# DoDecaCharlieCylonCR2032.net
KiCad netlist of a schematic drawn in EAGLE
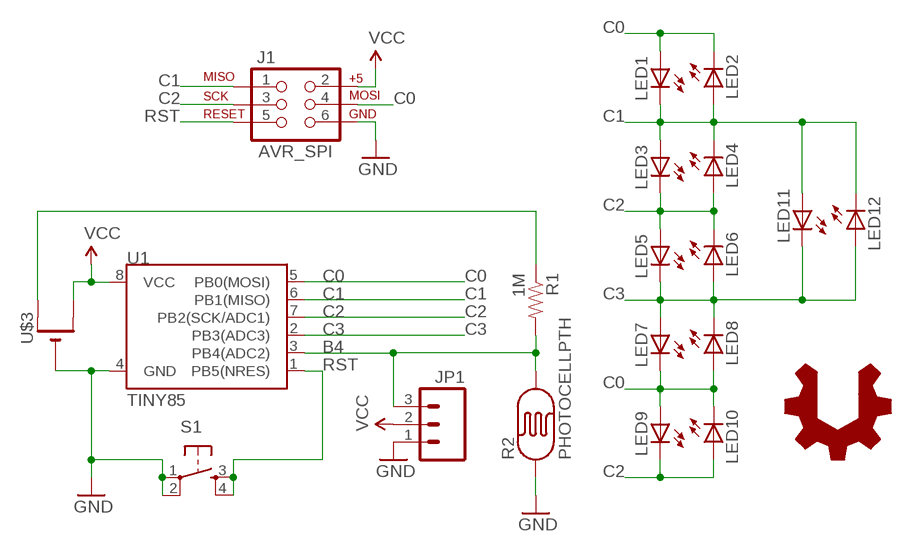
[diagram p0: schematic, sheet 1]

(export (version "E")
  (design (tool "Eeschema 10.0.6"))
  (components
    (comp (ref "J1")
      (value "AVR_SPI")
      (footprint "eagle-import:2X3-NS")
      (libsource (lib "eagle-import") (part "AVR_SPI_PRG_6LABELED"))
    )
    (comp (ref "JP1")
      (value "M03PTH")
      (footprint "eagle-import:1X03")
      (libsource (lib "eagle-import") (part "M03PTH"))
    )
    (comp (ref "LED1")
      (value "LEDOVAL")
      (footprint "eagle-import:LED-OVAL")
      (libsource (lib "eagle-import") (part "LEDOVAL"))
    )
    (comp (ref "LED2")
      (value "LEDOVAL")
      (footprint "eagle-import:LED-OVAL")
      (libsource (lib "eagle-import") (part "LEDOVAL"))
    )
    (comp (ref "LED3")
      (value "LEDOVAL")
      (footprint "eagle-import:LED-OVAL")
      (libsource (lib "eagle-import") (part "LEDOVAL"))
    )
    (comp (ref "LED4")
      (value "LEDOVAL")
      (footprint "eagle-import:LED-OVAL")
      (libsource (lib "eagle-import") (part "LEDOVAL"))
    )
    (comp (ref "LED5")
      (value "LEDOVAL")
      (footprint "eagle-import:LED-OVAL")
      (libsource (lib "eagle-import") (part "LEDOVAL"))
    )
    (comp (ref "LED6")
      (value "LEDOVAL")
      (footprint "eagle-import:LED-OVAL")
      (libsource (lib "eagle-import") (part "LEDOVAL"))
    )
    (comp (ref "LED7")
      (value "LEDOVAL")
      (footprint "eagle-import:LED-OVAL")
      (libsource (lib "eagle-import") (part "LEDOVAL"))
    )
    (comp (ref "LED8")
      (value "LEDOVAL")
      (footprint "eagle-import:LED-OVAL")
      (libsource (lib "eagle-import") (part "LEDOVAL"))
    )
    (comp (ref "LED9")
      (value "LEDOVAL")
      (footprint "eagle-import:LED-OVAL")
      (libsource (lib "eagle-import") (part "LEDOVAL"))
    )
    (comp (ref "LED10")
      (value "LEDOVAL")
      (footprint "eagle-import:LED-OVAL")
      (libsource (lib "eagle-import") (part "LEDOVAL"))
    )
    (comp (ref "LED11")
      (value "LEDOVAL")
      (footprint "eagle-import:LED-OVAL")
      (libsource (lib "eagle-import") (part "LEDOVAL"))
    )
    (comp (ref "LED12")
      (value "LEDOVAL")
      (footprint "eagle-import:LED-OVAL")
      (libsource (lib "eagle-import") (part "LEDOVAL"))
    )
    (comp (ref "R1")
      (value "1M")
      (footprint "eagle-import:AXIAL-0.3")
      (libsource (lib "eagle-import") (part "RESISTORAXIAL-0.3"))
    )
    (comp (ref "R2")
      (value "PHOTOCELLPTH")
      (footprint "eagle-import:PHOTOCELL")
      (libsource (lib "eagle-import") (part "PHOTOCELLPTH"))
    )
    (comp (ref "S1")
      (value "TAC_SWITCHPTH")
      (footprint "eagle-import:TACTILE-PTH")
      (libsource (lib "eagle-import") (part "TAC_SWITCHPTH"))
    )
    (comp (ref "U$1")
      (value "USER_HACKABLE")
      (footprint "eagle-import:USER_HACKABLE")
      (libsource (lib "eagle-import") (part "USER_HACKABLE"))
    )
    (comp (ref "U$3")
      (value "CR2032THM")
      (footprint "eagle-import:CR2032-THRU")
      (libsource (lib "eagle-import") (part "CR2032THM"))
    )
    (comp (ref "U1")
      (value "TINY85")
      (footprint "eagle-import:DIP08")
      (libsource (lib "eagle-import") (part "ATTINY45TINY85-20-DIP"))
    )
  )
  (nets
    (net (code "1") (name "/B4") (class "Default")
      (node (ref "JP1") (pin "3") (pinfunction "3_3") (pintype "passive"))
      (node (ref "R1") (pin "P$2") (pinfunction "2_P$2") (pintype "passive"))
      (node (ref "R2") (pin "2") (pinfunction "P$2_2") (pintype "bidirectional"))
      (node (ref "U1") (pin "3") (pinfunction "PB4(ADC2)_3") (pintype "bidirectional"))
    )
    (net (code "2") (name "/C0") (class "Default")
      (node (ref "J1") (pin "4") (pinfunction "MOSI_4") (pintype "passive"))
      (node (ref "LED1") (pin "ANODE") (pinfunction "A_ANODE") (pintype "passive"))
      (node (ref "LED10") (pin "CATHODE") (pinfunction "C_CATHODE") (pintype "passive"))
      (node (ref "LED2") (pin "CATHODE") (pinfunction "C_CATHODE") (pintype "passive"))
      (node (ref "LED7") (pin "CATHODE") (pinfunction "C_CATHODE") (pintype "passive"))
      (node (ref "LED8") (pin "ANODE") (pinfunction "A_ANODE") (pintype "passive"))
      (node (ref "LED9") (pin "ANODE") (pinfunction "A_ANODE") (pintype "passive"))
      (node (ref "U1") (pin "5") (pinfunction "PB0(MOSI)_5") (pintype "bidirectional"))
    )
    (net (code "3") (name "/C1") (class "Default")
      (node (ref "J1") (pin "1") (pinfunction "MISO_1") (pintype "passive"))
      (node (ref "LED1") (pin "CATHODE") (pinfunction "C_CATHODE") (pintype "passive"))
      (node (ref "LED11") (pin "ANODE") (pinfunction "A_ANODE") (pintype "passive"))
      (node (ref "LED12") (pin "CATHODE") (pinfunction "C_CATHODE") (pintype "passive"))
      (node (ref "LED2") (pin "ANODE") (pinfunction "A_ANODE") (pintype "passive"))
      (node (ref "LED3") (pin "ANODE") (pinfunction "A_ANODE") (pintype "passive"))
      (node (ref "LED4") (pin "CATHODE") (pinfunction "C_CATHODE") (pintype "passive"))
      (node (ref "U1") (pin "6") (pinfunction "PB1(MISO)_6") (pintype "bidirectional"))
    )
    (net (code "4") (name "/C2") (class "Default")
      (node (ref "J1") (pin "3") (pinfunction "SCK_3") (pintype "passive"))
      (node (ref "LED10") (pin "ANODE") (pinfunction "A_ANODE") (pintype "passive"))
      (node (ref "LED3") (pin "CATHODE") (pinfunction "C_CATHODE") (pintype "passive"))
      (node (ref "LED4") (pin "ANODE") (pinfunction "A_ANODE") (pintype "passive"))
      (node (ref "LED5") (pin "ANODE") (pinfunction "A_ANODE") (pintype "passive"))
      (node (ref "LED6") (pin "CATHODE") (pinfunction "C_CATHODE") (pintype "passive"))
      (node (ref "LED9") (pin "CATHODE") (pinfunction "C_CATHODE") (pintype "passive"))
      (node (ref "U1") (pin "7") (pinfunction "PB2(SCK/ADC1)_7") (pintype "bidirectional"))
    )
    (net (code "5") (name "/C3") (class "Default")
      (node (ref "LED11") (pin "CATHODE") (pinfunction "C_CATHODE") (pintype "passive"))
      (node (ref "LED12") (pin "ANODE") (pinfunction "A_ANODE") (pintype "passive"))
      (node (ref "LED5") (pin "CATHODE") (pinfunction "C_CATHODE") (pintype "passive"))
      (node (ref "LED6") (pin "ANODE") (pinfunction "A_ANODE") (pintype "passive"))
      (node (ref "LED7") (pin "ANODE") (pinfunction "A_ANODE") (pintype "passive"))
      (node (ref "LED8") (pin "CATHODE") (pinfunction "C_CATHODE") (pintype "passive"))
      (node (ref "U1") (pin "2") (pinfunction "PB3(ADC3)_2") (pintype "bidirectional"))
    )
    (net (code "6") (name "/RST") (class "Default")
      (node (ref "J1") (pin "5") (pinfunction "RST_5") (pintype "passive"))
      (node (ref "S1") (pin "3") (pinfunction "3_3") (pintype "passive"))
      (node (ref "S1") (pin "4") (pinfunction "4_4") (pintype "passive"))
      (node (ref "U1") (pin "1") (pinfunction "PB5(NRES)_1") (pintype "bidirectional"))
    )
    (net (code "7") (name "GND") (class "Default")
      (node (ref "J1") (pin "6") (pinfunction "GND_6") (pintype "passive"))
      (node (ref "JP1") (pin "1") (pinfunction "1_1") (pintype "passive"))
      (node (ref "R2") (pin "1") (pinfunction "P$1_1") (pintype "bidirectional"))
      (node (ref "S1") (pin "1") (pinfunction "1_1") (pintype "passive"))
      (node (ref "S1") (pin "2") (pinfunction "2_2") (pintype "passive"))
      (node (ref "U$3") (pin "-") (pinfunction "-_-") (pintype "passive"))
      (node (ref "U1") (pin "4") (pinfunction "GND_4") (pintype "bidirectional"))
    )
    (net (code "8") (name "Net-(R1-1)") (class "Default")
      (node (ref "R1") (pin "P$1") (pinfunction "1_P$1") (pintype "passive"))
      (node (ref "U$3") (pin "+1") (pinfunction "+_+1") (pintype "passive"))
    )
    (net (code "9") (name "VCC") (class "Default")
      (node (ref "J1") (pin "2") (pinfunction "V+_2") (pintype "passive"))
      (node (ref "JP1") (pin "2") (pinfunction "2_2") (pintype "passive"))
      (node (ref "U$3") (pin "+2") (pinfunction "+1_+2") (pintype "passive"))
      (node (ref "U1") (pin "8") (pinfunction "VCC_8") (pintype "bidirectional"))
    )
  )
)
